# 7-serial-interfaces.net
KiCad netlist of a schematic drawn in Altium Designer
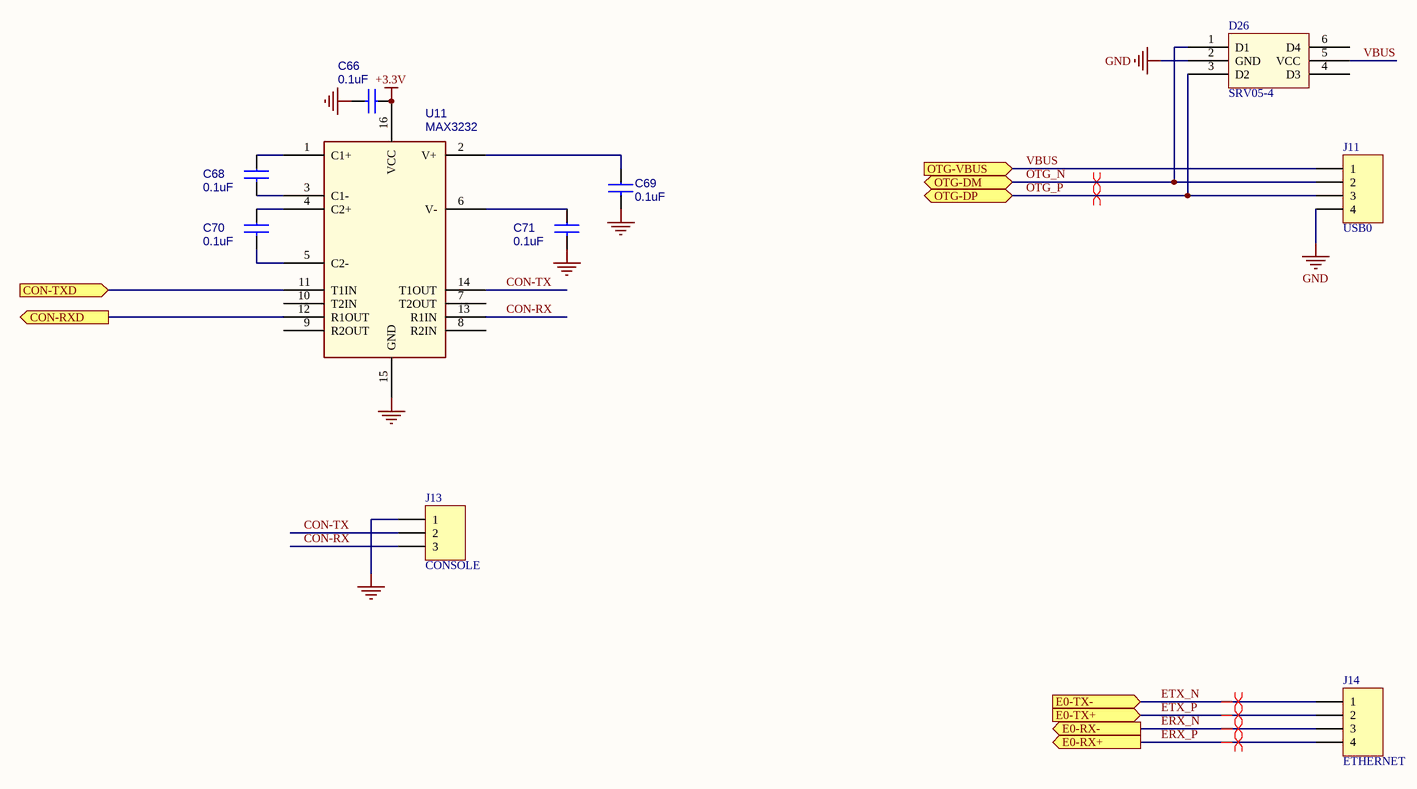
[diagram p0: 7-serial-interfaces.SchDoc]

(export (version "E")
  (design (tool "Eeschema 10.0.6"))
  (components
    (comp (ref "C66") (value "0.1uF") (libsource (lib "*") (part "CAP")))
    (comp (ref "C68") (value "0.1uF") (libsource (lib "*") (part "CAP")))
    (comp (ref "C69") (value "0.1uF") (libsource (lib "*") (part "CAP")))
    (comp (ref "C70") (value "0.1uF") (libsource (lib "*") (part "CAP")))
    (comp (ref "C71") (value "0.1uF") (libsource (lib "*") (part "CAP")))
    (comp (ref "D26") (value "SRV05-4") (footprint "SOT23-6") (libsource (lib "Schlib") (part "SRV05-4")))
    (comp (ref "J11")
      (value "USB0")
      (footprint "CON-4PIN")
      (description "Header, 4-Pin")
      (fields (field (name "PUBLISHER") "Altium Limited"))
      (libsource (lib "Miscellaneous Connectors") (part "Header 4"))
    )
    (comp (ref "J13")
      (value "CONSOLE")
      (footprint "CONN-3P")
      (description "Header, 3-Pin")
      (fields (field (name "PUBLISHER") "Altium Limited"))
      (libsource (lib "Miscellaneous Connectors") (part "Header 3"))
    )
    (comp (ref "J14")
      (value "ETHERNET")
      (footprint "CON-4PIN")
      (description "Header, 4-Pin")
      (fields (field (name "PUBLISHER") "Altium Limited"))
      (libsource (lib "Miscellaneous Connectors") (part "Header 4"))
    )
    (comp (ref "U11") (value "MAX3232") (footprint "SO-16") (libsource (lib "*") (part "MAX3232")))
  )
  (nets
    (net (code "1") (name "+3.3V") (class "Default")
      (node (ref "C66") (pin "1") (pinfunction "1_1") (pintype "passive"))
      (node (ref "U11") (pin "16") (pinfunction "VCC_16") (pintype "passive"))
    )
    (net (code "2") (name "/CON-RX") (class "Default")
      (node (ref "J13") (pin "3") (pinfunction "3_3") (pintype "passive"))
      (node (ref "U11") (pin "13") (pinfunction "R1IN_13") (pintype "passive"))
    )
    (net (code "3") (name "/CON-RXD") (class "Default")
      (node (ref "U11") (pin "12") (pinfunction "R1OUT_12") (pintype "passive"))
    )
    (net (code "4") (name "/CON-TX") (class "Default")
      (node (ref "J13") (pin "2") (pinfunction "2_2") (pintype "passive"))
      (node (ref "U11") (pin "14") (pinfunction "T1OUT_14") (pintype "passive"))
    )
    (net (code "5") (name "/CON-TXD") (class "Default")
      (node (ref "U11") (pin "11") (pinfunction "T1IN_11") (pintype "passive"))
    )
    (net (code "6") (name "/ERX_N") (class "Default")
      (node (ref "J14") (pin "3") (pinfunction "3_3") (pintype "passive"))
    )
    (net (code "7") (name "/ERX_P") (class "Default")
      (node (ref "J14") (pin "4") (pinfunction "4_4") (pintype "passive"))
    )
    (net (code "8") (name "/ETX_N") (class "Default")
      (node (ref "J14") (pin "1") (pinfunction "1_1") (pintype "passive"))
    )
    (net (code "9") (name "/ETX_P") (class "Default")
      (node (ref "J14") (pin "2") (pinfunction "2_2") (pintype "passive"))
    )
    (net (code "10") (name "/OTG_N") (class "Default")
      (node (ref "D26") (pin "1") (pinfunction "D1_1") (pintype "passive"))
      (node (ref "J11") (pin "2") (pinfunction "2_2") (pintype "passive"))
    )
    (net (code "11") (name "/OTG_P") (class "Default")
      (node (ref "D26") (pin "3") (pinfunction "D2_3") (pintype "passive"))
      (node (ref "J11") (pin "3") (pinfunction "3_3") (pintype "passive"))
    )
    (net (code "12") (name "/VBUS") (class "Default")
      (node (ref "D26") (pin "5") (pinfunction "VCC_5") (pintype "passive"))
      (node (ref "J11") (pin "1") (pinfunction "1_1") (pintype "passive"))
    )
    (net (code "13") (name "GND") (class "Default")
      (node (ref "C66") (pin "2") (pinfunction "2_2") (pintype "passive"))
      (node (ref "C69") (pin "2") (pinfunction "2_2") (pintype "passive"))
      (node (ref "C71") (pin "2") (pinfunction "2_2") (pintype "passive"))
      (node (ref "D26") (pin "2") (pinfunction "GND_2") (pintype "passive"))
      (node (ref "J11") (pin "4") (pinfunction "4_4") (pintype "passive"))
      (node (ref "J13") (pin "1") (pinfunction "1_1") (pintype "passive"))
      (node (ref "U11") (pin "15") (pinfunction "GND_15") (pintype "passive"))
    )
    (net (code "14") (name "Net-(U11-C1+)") (class "Default")
      (node (ref "C68") (pin "1") (pinfunction "1_1") (pintype "passive"))
      (node (ref "U11") (pin "1") (pinfunction "C1+_1") (pintype "passive"))
    )
    (net (code "15") (name "Net-(U11-C1-)") (class "Default")
      (node (ref "C68") (pin "2") (pinfunction "2_2") (pintype "passive"))
      (node (ref "U11") (pin "3") (pinfunction "C1-_3") (pintype "passive"))
    )
    (net (code "16") (name "Net-(U11-C2+)") (class "Default")
      (node (ref "C70") (pin "1") (pinfunction "1_1") (pintype "passive"))
      (node (ref "U11") (pin "4") (pinfunction "C2+_4") (pintype "passive"))
    )
    (net (code "17") (name "Net-(U11-C2-)") (class "Default")
      (node (ref "C70") (pin "2") (pinfunction "2_2") (pintype "passive"))
      (node (ref "U11") (pin "5") (pinfunction "C2-_5") (pintype "passive"))
    )
    (net (code "18") (name "Net-(U11-V+)") (class "Default")
      (node (ref "C69") (pin "1") (pinfunction "1_1") (pintype "passive"))
      (node (ref "U11") (pin "2") (pinfunction "V+_2") (pintype "passive"))
    )
    (net (code "19") (name "Net-(U11-V-)") (class "Default")
      (node (ref "C71") (pin "1") (pinfunction "1_1") (pintype "passive"))
      (node (ref "U11") (pin "6") (pinfunction "V-_6") (pintype "passive"))
    )
    (net (code "20") (name "unconnected-(D26-D3-Pad4)") (class "Default")
      (node (ref "D26") (pin "4") (pinfunction "D3_4") (pintype "passive"))
    )
    (net (code "21") (name "unconnected-(D26-D4-Pad6)") (class "Default")
      (node (ref "D26") (pin "6") (pinfunction "D4_6") (pintype "passive"))
    )
    (net (code "22") (name "unconnected-(U11-R2IN-Pad8)") (class "Default")
      (node (ref "U11") (pin "8") (pinfunction "R2IN_8") (pintype "passive"))
    )
    (net (code "23") (name "unconnected-(U11-R2OUT-Pad9)") (class "Default")
      (node (ref "U11") (pin "9") (pinfunction "R2OUT_9") (pintype "passive"))
    )
    (net (code "24") (name "unconnected-(U11-T2IN-Pad10)") (class "Default")
      (node (ref "U11") (pin "10") (pinfunction "T2IN_10") (pintype "passive"))
    )
    (net (code "25") (name "unconnected-(U11-T2OUT-Pad7)") (class "Default")
      (node (ref "U11") (pin "7") (pinfunction "T2OUT_7") (pintype "passive"))
    )
  )
)
